# corridor_distal.net
KiCad netlist of a schematic drawn in EAGLE
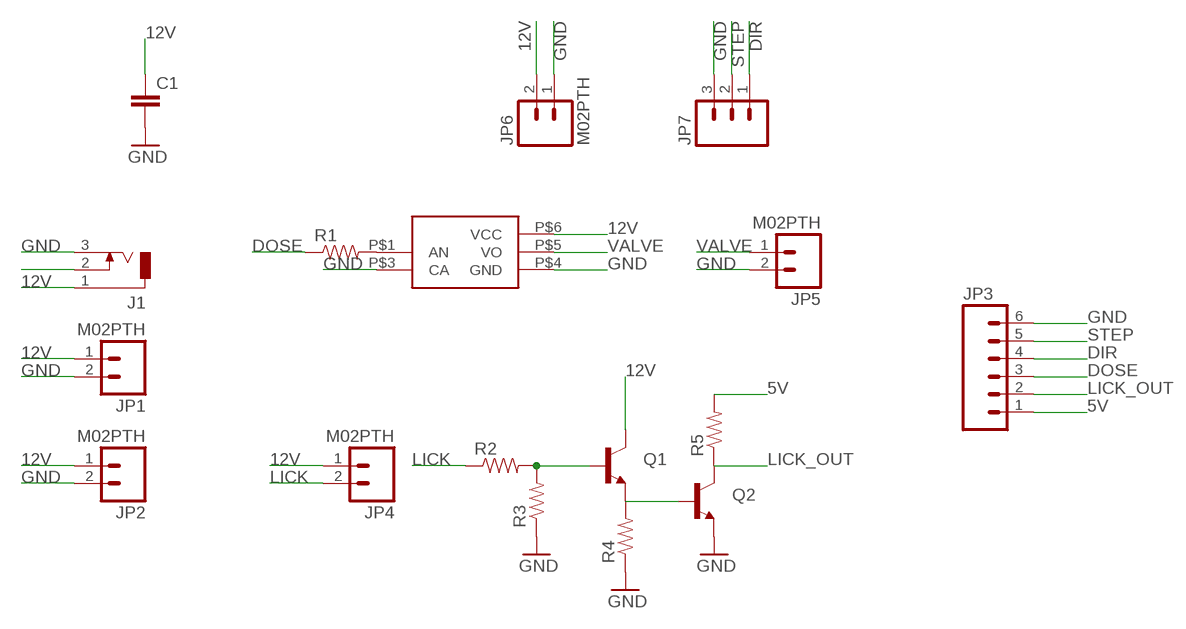
[diagram p0: schematic, sheet 1]

(export (version "E")
  (design (tool "Eeschema 10.0.6"))
  (components
    (comp (ref "C1")
      (value "CAP1206")
      (footprint "eagle-import:1206")
      (libsource (lib "eagle-import") (part "CAP1206"))
    )
    (comp (ref "J1")
      (value "DCJ0303")
      (footprint "eagle-import:DCJ0303")
      (libsource (lib "eagle-import") (part "DCJ0303"))
    )
    (comp (ref "JP1")
      (value "M02PTH")
      (footprint "eagle-import:1X02")
      (libsource (lib "eagle-import") (part "M02PTH"))
    )
    (comp (ref "JP2")
      (value "M02PTH")
      (footprint "eagle-import:1X02")
      (libsource (lib "eagle-import") (part "M02PTH"))
    )
    (comp (ref "JP3")
      (value "M06SIP")
      (footprint "eagle-import:1X06")
      (libsource (lib "eagle-import") (part "M06SIP"))
    )
    (comp (ref "JP4")
      (value "M02PTH")
      (footprint "eagle-import:1X02")
      (libsource (lib "eagle-import") (part "M02PTH"))
    )
    (comp (ref "JP5")
      (value "M02PTH")
      (footprint "eagle-import:1X02")
      (libsource (lib "eagle-import") (part "M02PTH"))
    )
    (comp (ref "JP6")
      (value "M02PTH")
      (footprint "eagle-import:1X02")
      (libsource (lib "eagle-import") (part "M02PTH"))
    )
    (comp (ref "JP7")
      (value "M03PTH")
      (footprint "eagle-import:1X03")
      (libsource (lib "eagle-import") (part "M03PTH"))
    )
    (comp (ref "Q1")
      (value "TRANSISTOR_NPNTO92")
      (footprint "eagle-import:TO-92")
      (libsource (lib "eagle-import") (part "TRANSISTOR_NPNTO92"))
    )
    (comp (ref "Q2")
      (value "TRANSISTOR_NPNTO92")
      (footprint "eagle-import:TO-92")
      (libsource (lib "eagle-import") (part "TRANSISTOR_NPNTO92"))
    )
    (comp (ref "R1")
      (value "RESISTOR1206")
      (footprint "eagle-import:1206")
      (libsource (lib "eagle-import") (part "RESISTOR1206"))
    )
    (comp (ref "R2")
      (value "RESISTOR1206")
      (footprint "eagle-import:1206")
      (libsource (lib "eagle-import") (part "RESISTOR1206"))
    )
    (comp (ref "R3")
      (value "RESISTOR1206")
      (footprint "eagle-import:1206")
      (libsource (lib "eagle-import") (part "RESISTOR1206"))
    )
    (comp (ref "R4")
      (value "RESISTOR1206")
      (footprint "eagle-import:1206")
      (libsource (lib "eagle-import") (part "RESISTOR1206"))
    )
    (comp (ref "R5")
      (value "RESISTOR1206")
      (footprint "eagle-import:1206")
      (libsource (lib "eagle-import") (part "RESISTOR1206"))
    )
    (comp (ref "U$1")
      (value "TLP701")
      (footprint "eagle-import:TLP701")
      (libsource (lib "eagle-import") (part "TLP701"))
    )
  )
  (nets
    (net (code "1") (name "/5V") (class "Default")
      (node (ref "JP3") (pin "1") (pinfunction "1_1") (pintype "passive"))
      (node (ref "R5") (pin "2") (pinfunction "2_2") (pintype "passive"))
    )
    (net (code "2") (name "/12V") (class "Default")
      (node (ref "C1") (pin "1") (pinfunction "1_1") (pintype "passive"))
      (node (ref "J1") (pin "1") (pinfunction "1_1") (pintype "passive"))
      (node (ref "JP1") (pin "1") (pinfunction "1_1") (pintype "passive"))
      (node (ref "JP2") (pin "1") (pinfunction "1_1") (pintype "passive"))
      (node (ref "JP4") (pin "1") (pinfunction "1_1") (pintype "passive"))
      (node (ref "JP6") (pin "2") (pinfunction "2_2") (pintype "passive"))
      (node (ref "Q1") (pin "3") (pinfunction "C_3") (pintype "passive"))
      (node (ref "U$1") (pin "P$6") (pinfunction "VCC_P$6") (pintype "bidirectional"))
    )
    (net (code "3") (name "/DIR") (class "Default")
      (node (ref "JP3") (pin "4") (pinfunction "4_4") (pintype "passive"))
      (node (ref "JP7") (pin "1") (pinfunction "1_1") (pintype "passive"))
    )
    (net (code "4") (name "/DOSE") (class "Default")
      (node (ref "JP3") (pin "3") (pinfunction "3_3") (pintype "passive"))
      (node (ref "R1") (pin "1") (pinfunction "1_1") (pintype "passive"))
    )
    (net (code "5") (name "/LICK") (class "Default")
      (node (ref "JP4") (pin "2") (pinfunction "2_2") (pintype "passive"))
      (node (ref "R2") (pin "1") (pinfunction "1_1") (pintype "passive"))
    )
    (net (code "6") (name "/LICK_OUT") (class "Default")
      (node (ref "JP3") (pin "2") (pinfunction "2_2") (pintype "passive"))
      (node (ref "Q2") (pin "3") (pinfunction "C_3") (pintype "passive"))
      (node (ref "R5") (pin "1") (pinfunction "1_1") (pintype "passive"))
    )
    (net (code "7") (name "/STEP") (class "Default")
      (node (ref "JP3") (pin "5") (pinfunction "5_5") (pintype "passive"))
      (node (ref "JP7") (pin "2") (pinfunction "2_2") (pintype "passive"))
    )
    (net (code "8") (name "/VALVE") (class "Default")
      (node (ref "JP5") (pin "1") (pinfunction "1_1") (pintype "passive"))
      (node (ref "U$1") (pin "P$5") (pinfunction "VO_P$5") (pintype "bidirectional"))
    )
    (net (code "9") (name "GND") (class "Default")
      (node (ref "C1") (pin "2") (pinfunction "2_2") (pintype "passive"))
      (node (ref "J1") (pin "3") (pinfunction "3_3") (pintype "passive"))
      (node (ref "JP1") (pin "2") (pinfunction "2_2") (pintype "passive"))
      (node (ref "JP2") (pin "2") (pinfunction "2_2") (pintype "passive"))
      (node (ref "JP3") (pin "6") (pinfunction "6_6") (pintype "passive"))
      (node (ref "JP5") (pin "2") (pinfunction "2_2") (pintype "passive"))
      (node (ref "JP6") (pin "1") (pinfunction "1_1") (pintype "passive"))
      (node (ref "JP7") (pin "3") (pinfunction "3_3") (pintype "passive"))
      (node (ref "Q2") (pin "1") (pinfunction "E_1") (pintype "passive"))
      (node (ref "R3") (pin "1") (pinfunction "1_1") (pintype "passive"))
      (node (ref "R4") (pin "1") (pinfunction "1_1") (pintype "passive"))
      (node (ref "U$1") (pin "P$3") (pinfunction "CA_P$3") (pintype "bidirectional"))
      (node (ref "U$1") (pin "P$4") (pinfunction "GND_P$4") (pintype "bidirectional"))
    )
    (net (code "10") (name "Net-(Q1-B)") (class "Default")
      (node (ref "Q1") (pin "2") (pinfunction "B_2") (pintype "passive"))
      (node (ref "R2") (pin "2") (pinfunction "2_2") (pintype "passive"))
      (node (ref "R3") (pin "2") (pinfunction "2_2") (pintype "passive"))
    )
    (net (code "11") (name "Net-(Q1-E)") (class "Default")
      (node (ref "Q1") (pin "1") (pinfunction "E_1") (pintype "passive"))
      (node (ref "Q2") (pin "2") (pinfunction "B_2") (pintype "passive"))
      (node (ref "R4") (pin "2") (pinfunction "2_2") (pintype "passive"))
    )
    (net (code "12") (name "Net-(U$1-AN)") (class "Default")
      (node (ref "R1") (pin "2") (pinfunction "2_2") (pintype "passive"))
      (node (ref "U$1") (pin "P$1") (pinfunction "AN_P$1") (pintype "bidirectional"))
    )
    (net (code "13") (name "unconnected-(J1-Pad2)") (class "Default")
      (node (ref "J1") (pin "2") (pinfunction "2_2") (pintype "passive"))
    )
  )
)
